# CHECK.net
KiCad netlist of a schematic drawn in Altium Designer
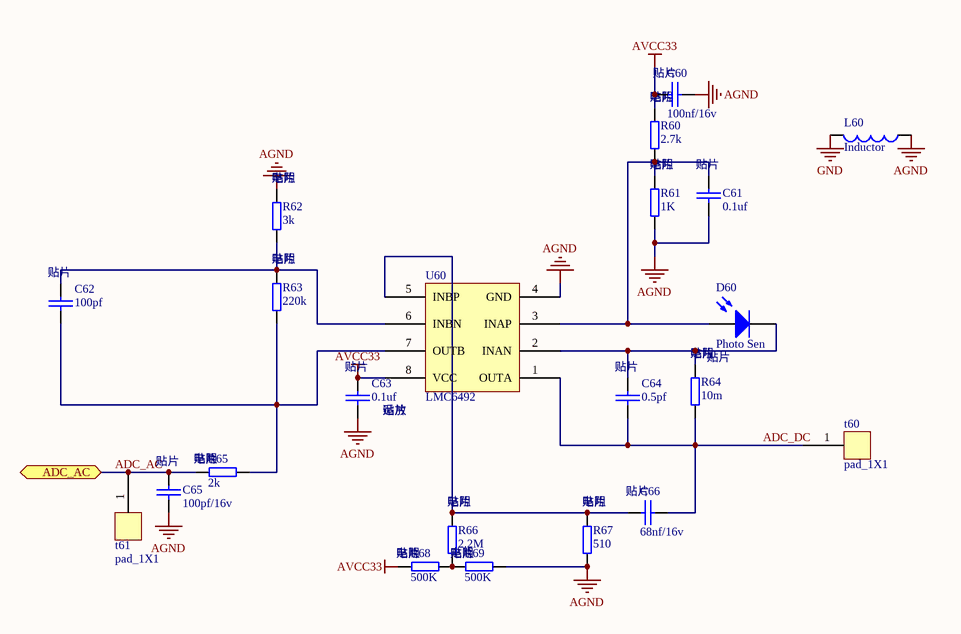
[diagram p0: CHECK.SchDoc]

(export (version "E")
  (design (tool "Eeschema 10.0.6"))
  (components
    (comp (ref "C60")
      (value "100nf/16v")
      (footprint "C0402")
      (description "C")
      (libsource (lib "CxyDXP_SCH") (part "CC"))
    )
    (comp (ref "C61")
      (value "0.1uf")
      (footprint "C0402")
      (description "C")
      (libsource (lib "CxyDXP_SCH") (part "CC"))
    )
    (comp (ref "C62")
      (value "100pf")
      (footprint "C0402")
      (description "C")
      (libsource (lib "CxyDXP_SCH") (part "CC"))
    )
    (comp (ref "C63")
      (value "0.1uf")
      (footprint "C0402")
      (description "C")
      (libsource (lib "CxyDXP_SCH") (part "CC"))
    )
    (comp (ref "C64")
      (value "0.5pf")
      (footprint "C0402")
      (description "C")
      (libsource (lib "CxyDXP_SCH") (part "CC"))
    )
    (comp (ref "C65")
      (value "100pf/16v")
      (footprint "C0402")
      (description "C")
      (libsource (lib "CxyDXP_SCH") (part "CC"))
    )
    (comp (ref "C66")
      (value "68nf/16v")
      (footprint "C0402")
      (description "C")
      (libsource (lib "CxyDXP_SCH") (part "CC"))
    )
    (comp (ref "D60")
      (value "Photo Sen")
      (footprint "PhotoSen")
      (description "Photosensitive Diode")
      (libsource (lib "Miscellaneous Devices") (part "Photo Sen"))
    )
    (comp (ref "L60")
      (value "Inductor")
      (footprint "L0402")
      (fields (field (name "PUBLISHER") "Altium Limited"))
      (libsource (lib "Miscellaneous Devices") (part "Inductor"))
    )
    (comp (ref "R60")
      (value "2.7k")
      (footprint "R0402")
      (description "R")
      (libsource (lib "CxyDXP_SCH") (part "RES1"))
    )
    (comp (ref "R61")
      (value "1K")
      (footprint "R0402")
      (description "R")
      (libsource (lib "CxyDXP_SCH") (part "RES1"))
    )
    (comp (ref "R62")
      (value "3k")
      (footprint "R0402")
      (description "R")
      (libsource (lib "CxyDXP_SCH") (part "RES1"))
    )
    (comp (ref "R63")
      (value "220k")
      (footprint "R0402")
      (description "R")
      (libsource (lib "CxyDXP_SCH") (part "RES1"))
    )
    (comp (ref "R64")
      (value "10m")
      (footprint "R0402")
      (description "R")
      (libsource (lib "CxyDXP_SCH") (part "RES1"))
    )
    (comp (ref "R65")
      (value "2k")
      (footprint "R0402")
      (description "R")
      (libsource (lib "CxyDXP_SCH") (part "RES1"))
    )
    (comp (ref "R66")
      (value "2.2M")
      (footprint "R0402")
      (description "R")
      (libsource (lib "CxyDXP_SCH") (part "RES1"))
    )
    (comp (ref "R67")
      (value "510")
      (footprint "R0402")
      (description "R")
      (libsource (lib "CxyDXP_SCH") (part "RES1"))
    )
    (comp (ref "R68")
      (value "500K")
      (footprint "R0402")
      (description "R")
      (libsource (lib "CxyDXP_SCH") (part "RES1"))
    )
    (comp (ref "R69")
      (value "500K")
      (footprint "R0402")
      (description "R")
      (libsource (lib "CxyDXP_SCH") (part "RES1"))
    )
    (comp (ref "t60") (value "pad_1X1") (footprint "pad_0603") (libsource (lib "DUST") (part "pad_1X1")))
    (comp (ref "t61") (value "pad_1X1") (footprint "pad_0603") (libsource (lib "") (part "pad_1X1_1")))
    (comp (ref "U60") (value "LMC6492") (footprint "SO-8") (libsource (lib "DUST") (part "LMC6492")))
  )
  (nets
    (net (code "1") (name "/ADC_AC") (class "Default")
      (node (ref "C65") (pin "2") (pintype "passive"))
      (node (ref "R65") (pin "1") (pinfunction "1_1") (pintype "passive"))
      (node (ref "t61") (pin "1") (pintype "passive"))
    )
    (net (code "2") (name "/ADC_DC") (class "Default")
      (node (ref "C64") (pin "2") (pintype "passive"))
      (node (ref "C66") (pin "2") (pintype "passive"))
      (node (ref "R64") (pin "2") (pinfunction "2_2") (pintype "passive"))
      (node (ref "U60") (pin "1") (pinfunction "OUTA_1") (pintype "passive"))
      (node (ref "t60") (pin "1") (pintype "passive"))
    )
    (net (code "3") (name "AGND") (class "Default")
      (node (ref "C60") (pin "2") (pintype "passive"))
      (node (ref "C61") (pin "2") (pintype "passive"))
      (node (ref "C63") (pin "2") (pintype "passive"))
      (node (ref "C65") (pin "1") (pintype "passive"))
      (node (ref "L60") (pin "1") (pinfunction "1_1") (pintype "passive"))
      (node (ref "R61") (pin "2") (pinfunction "2_2") (pintype "passive"))
      (node (ref "R62") (pin "1") (pinfunction "1_1") (pintype "passive"))
      (node (ref "R67") (pin "2") (pinfunction "2_2") (pintype "passive"))
      (node (ref "R69") (pin "2") (pinfunction "2_2") (pintype "passive"))
      (node (ref "U60") (pin "4") (pinfunction "GND_4") (pintype "passive"))
    )
    (net (code "4") (name "AVCC33") (class "Default")
      (node (ref "C60") (pin "1") (pintype "passive"))
      (node (ref "C63") (pin "1") (pintype "passive"))
      (node (ref "R60") (pin "1") (pinfunction "1_1") (pintype "passive"))
      (node (ref "R68") (pin "1") (pinfunction "1_1") (pintype "passive"))
      (node (ref "U60") (pin "8") (pinfunction "VCC_8") (pintype "passive"))
    )
    (net (code "5") (name "GND") (class "Default")
      (node (ref "L60") (pin "2") (pinfunction "2_2") (pintype "passive"))
    )
    (net (code "6") (name "Net-(D60-A)") (class "Default")
      (node (ref "C61") (pin "1") (pintype "passive"))
      (node (ref "D60") (pin "1") (pinfunction "A_1") (pintype "passive"))
      (node (ref "R60") (pin "2") (pinfunction "2_2") (pintype "passive"))
      (node (ref "R61") (pin "1") (pinfunction "1_1") (pintype "passive"))
      (node (ref "U60") (pin "3") (pinfunction "INAP_3") (pintype "passive"))
    )
    (net (code "7") (name "Net-(D60-K)") (class "Default")
      (node (ref "C64") (pin "1") (pintype "passive"))
      (node (ref "D60") (pin "2") (pinfunction "K_2") (pintype "passive"))
      (node (ref "R64") (pin "1") (pinfunction "1_1") (pintype "passive"))
      (node (ref "U60") (pin "2") (pinfunction "INAN_2") (pintype "passive"))
    )
    (net (code "8") (name "Net-(R66-Pad2)") (class "Default")
      (node (ref "R66") (pin "2") (pinfunction "2_2") (pintype "passive"))
      (node (ref "R68") (pin "2") (pinfunction "2_2") (pintype "passive"))
      (node (ref "R69") (pin "1") (pinfunction "1_1") (pintype "passive"))
    )
    (net (code "9") (name "Net-(U60-INBN)") (class "Default")
      (node (ref "C62") (pin "1") (pintype "passive"))
      (node (ref "R62") (pin "2") (pinfunction "2_2") (pintype "passive"))
      (node (ref "R63") (pin "1") (pinfunction "1_1") (pintype "passive"))
      (node (ref "U60") (pin "6") (pinfunction "INBN_6") (pintype "passive"))
    )
    (net (code "10") (name "Net-(U60-INBP)") (class "Default")
      (node (ref "C66") (pin "1") (pintype "passive"))
      (node (ref "R66") (pin "1") (pinfunction "1_1") (pintype "passive"))
      (node (ref "R67") (pin "1") (pinfunction "1_1") (pintype "passive"))
      (node (ref "U60") (pin "5") (pinfunction "INBP_5") (pintype "passive"))
    )
    (net (code "11") (name "Net-(U60-OUTB)") (class "Default")
      (node (ref "C62") (pin "2") (pintype "passive"))
      (node (ref "R63") (pin "2") (pinfunction "2_2") (pintype "passive"))
      (node (ref "R65") (pin "2") (pinfunction "2_2") (pintype "passive"))
      (node (ref "U60") (pin "7") (pinfunction "OUTB_7") (pintype "passive"))
    )
  )
)
